# fat.net
KiCad netlist of a schematic drawn in Altium Designer
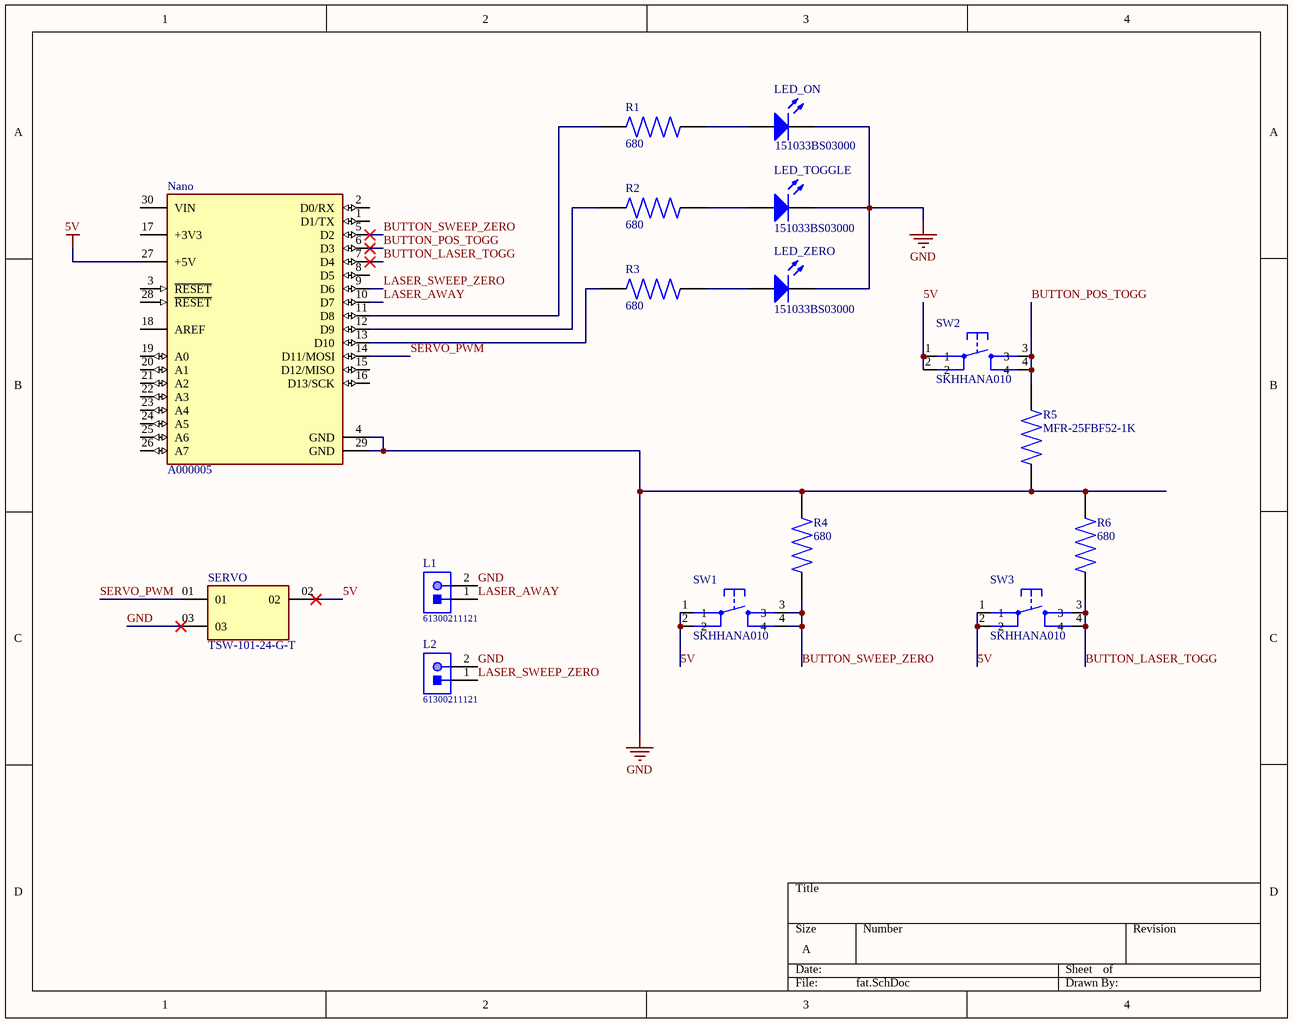
[diagram p0: fat.SchDoc]

(export (version "E")
  (design (tool "Eeschema 10.0.6"))
  (components
    (comp (ref "L1")
      (value "61300211121")
      (footprint "61300211121")
      (description "THT Vertical Pin Header WR-PHD, Pitch 2.54 mm, Single Row, 2 pins")
      (fields (field (name "MANUFACTURER") "Wurth Elektronik") (field (name "PUBLISHER") "WurthElektronik"))
      (libsource (lib "Altium Content Vault") (part "WE-CN-1P-M-R2"))
    )
    (comp (ref "L2")
      (value "61300211121")
      (footprint "61300211121")
      (description "THT Vertical Pin Header WR-PHD, Pitch 2.54 mm, Single Row, 2 pins")
      (fields (field (name "MANUFACTURER") "Wurth Elektronik") (field (name "PUBLISHER") "WurthElektronik"))
      (libsource (lib "Altium Content Vault") (part "WE-CN-1P-M-R2"))
    )
    (comp (ref "LED_ON")
      (value "151033BS03000")
      (footprint "Type 3mm")
      (description "THT LED round mono-color waterclear, WL-TMRW , Blue")
      (fields (field (name "MANUFACTURER") "Wuerth Elektronik"))
      (libsource (lib "Altium Content Vault") (part "WE-LED_K1A2-2"))
    )
    (comp (ref "LED_TOGGLE")
      (value "151033BS03000")
      (footprint "Type 3mm")
      (description "THT LED round mono-color waterclear, WL-TMRW , Blue")
      (fields (field (name "MANUFACTURER") "Wuerth Elektronik"))
      (libsource (lib "Altium Content Vault") (part "WE-LED_K1A2-2"))
    )
    (comp (ref "LED_ZERO")
      (value "151033BS03000")
      (footprint "Type 3mm")
      (description "THT LED round mono-color waterclear, WL-TMRW , Blue")
      (fields (field (name "MANUFACTURER") "Wuerth Elektronik"))
      (libsource (lib "Altium Content Vault") (part "WE-LED_K1A2-2"))
    )
    (comp (ref "Nano")
      (value "A000005")
      (footprint "FP-A000005-MFG")
      (description "ARDUINO NANO ATMEGA328 EVAL BRD")
      (libsource (lib "Altium Content Vault") (part "d190c066e99afd1c6882cf92e11b2cc"))
    )
    (comp (ref "R1")
      (value "680")
      (footprint "RESAD1100W55L680D260")
      (description "1.07 kOhms Â±1% 0.25W, 1/4W Through Hole Resistor Axial - Metal Film")
      (fields (field (name "MF") "Yageo") (field (name "MP") "MFR-25FBF52-1K"))
      (libsource (lib "MFR-25FBF52-1K") (part "MFR-25FBF52-1K"))
    )
    (comp (ref "R2")
      (value "680")
      (footprint "RESAD1100W55L680D260")
      (description "1.07 kOhms Â±1% 0.25W, 1/4W Through Hole Resistor Axial - Metal Film")
      (fields (field (name "MF") "Yageo") (field (name "MP") "MFR-25FBF52-1K"))
      (libsource (lib "MFR-25FBF52-1K") (part "MFR-25FBF52-1K"))
    )
    (comp (ref "R3")
      (value "680")
      (footprint "RESAD1100W55L680D260")
      (description "1.07 kOhms Â±1% 0.25W, 1/4W Through Hole Resistor Axial - Metal Film")
      (fields (field (name "MF") "Yageo") (field (name "MP") "MFR-25FBF52-1K"))
      (libsource (lib "MFR-25FBF52-1K") (part "MFR-25FBF52-1K"))
    )
    (comp (ref "R4")
      (value "680")
      (footprint "RESAD1100W55L680D260")
      (description "1.07 kOhms Â±1% 0.25W, 1/4W Through Hole Resistor Axial - Metal Film")
      (fields (field (name "MF") "Yageo") (field (name "MP") "MFR-25FBF52-1K"))
      (libsource (lib "MFR-25FBF52-1K") (part "MFR-25FBF52-1K"))
    )
    (comp (ref "R5")
      (value "MFR-25FBF52-1K")
      (footprint "RESAD1100W55L680D260")
      (description "1.07 kOhms Â±1% 0.25W, 1/4W Through Hole Resistor Axial - Metal Film")
      (fields (field (name "MF") "Yageo"))
      (libsource (lib "MFR-25FBF52-1K") (part "MFR-25FBF52-1K"))
    )
    (comp (ref "R6")
      (value "680")
      (footprint "RESAD1100W55L680D260")
      (description "1.07 kOhms Â±1% 0.25W, 1/4W Through Hole Resistor Axial - Metal Film")
      (fields (field (name "MF") "Yageo") (field (name "MP") "MFR-25FBF52-1K"))
      (libsource (lib "MFR-25FBF52-1K") (part "MFR-25FBF52-1K"))
    )
    (comp (ref "SERVO")
      (value "TSW-101-24-G-T")
      (footprint "SAMTEC_TSW-101-24-G-T")
      (description "Connector Header Through Hole 3 position -")
      (fields (field (name "MF") "Samtec"))
      (libsource (lib "TSW-101-24-G-T") (part "TSW-101-24-G-T"))
    )
    (comp (ref "SW1")
      (value "SKHHANA010")
      (footprint "SW_SKHHANA010")
      (description "Switch Tactile N.O. SPST Round Button PC Pins 0.05A 12VDC 0.98N Thru-Hole Bulk")
      (fields (field (name "MF") "ALPS"))
      (libsource (lib "SKHHANA010") (part "SKHHANA010"))
    )
    (comp (ref "SW2")
      (value "SKHHANA010")
      (footprint "SW_SKHHANA010")
      (description "Switch Tactile N.O. SPST Round Button PC Pins 0.05A 12VDC 0.98N Thru-Hole Bulk")
      (fields (field (name "MF") "ALPS"))
      (libsource (lib "SKHHANA010") (part "SKHHANA010"))
    )
    (comp (ref "SW3")
      (value "SKHHANA010")
      (footprint "SW_SKHHANA010")
      (description "Switch Tactile N.O. SPST Round Button PC Pins 0.05A 12VDC 0.98N Thru-Hole Bulk")
      (fields (field (name "MF") "ALPS"))
      (libsource (lib "SKHHANA010") (part "SKHHANA010"))
    )
  )
  (nets
    (net (code "1") (name "/BUTTON_LASER_TOGG") (class "Default")
      (node (ref "Nano") (pin "7") (pinfunction "D4_7") (pintype "bidirectional"))
      (node (ref "R6") (pin "2") (pinfunction "2_2") (pintype "passive"))
      (node (ref "SW3") (pin "3") (pinfunction "3_3") (pintype "passive"))
      (node (ref "SW3") (pin "4") (pinfunction "4_4") (pintype "passive"))
    )
    (net (code "2") (name "/BUTTON_POS_TOGG") (class "Default")
      (node (ref "Nano") (pin "6") (pinfunction "D3_6") (pintype "bidirectional"))
      (node (ref "R5") (pin "1") (pinfunction "1_1") (pintype "passive"))
      (node (ref "SW2") (pin "3") (pinfunction "3_3") (pintype "passive"))
      (node (ref "SW2") (pin "4") (pinfunction "4_4") (pintype "passive"))
    )
    (net (code "3") (name "/BUTTON_SWEEP_ZERO") (class "Default")
      (node (ref "Nano") (pin "5") (pinfunction "D2_5") (pintype "bidirectional"))
      (node (ref "R4") (pin "2") (pinfunction "2_2") (pintype "passive"))
      (node (ref "SW1") (pin "3") (pinfunction "3_3") (pintype "passive"))
      (node (ref "SW1") (pin "4") (pinfunction "4_4") (pintype "passive"))
    )
    (net (code "4") (name "/LASER_AWAY") (class "Default")
      (node (ref "L1") (pin "1") (pinfunction "1_1") (pintype "passive"))
      (node (ref "Nano") (pin "10") (pinfunction "D7_10") (pintype "bidirectional"))
    )
    (net (code "5") (name "/LASER_SWEEP_ZERO") (class "Default")
      (node (ref "L2") (pin "1") (pinfunction "1_1") (pintype "passive"))
      (node (ref "Nano") (pin "9") (pinfunction "D6_9") (pintype "bidirectional"))
    )
    (net (code "6") (name "/SERVO_PWM") (class "Default")
      (node (ref "Nano") (pin "14") (pinfunction "D11/MOSI_14") (pintype "bidirectional"))
      (node (ref "SERVO") (pin "01") (pinfunction "01_01") (pintype "passive"))
    )
    (net (code "7") (name "5V") (class "Default")
      (node (ref "Nano") (pin "27") (pinfunction "+5V_27") (pintype "power_in"))
      (node (ref "SERVO") (pin "02") (pinfunction "02_02") (pintype "passive"))
      (node (ref "SW1") (pin "1") (pinfunction "1_1") (pintype "passive"))
      (node (ref "SW1") (pin "2") (pinfunction "2_2") (pintype "passive"))
      (node (ref "SW2") (pin "1") (pinfunction "1_1") (pintype "passive"))
      (node (ref "SW2") (pin "2") (pinfunction "2_2") (pintype "passive"))
      (node (ref "SW3") (pin "1") (pinfunction "1_1") (pintype "passive"))
      (node (ref "SW3") (pin "2") (pinfunction "2_2") (pintype "passive"))
    )
    (net (code "8") (name "GND") (class "Default")
      (node (ref "L1") (pin "2") (pinfunction "2_2") (pintype "passive"))
      (node (ref "L2") (pin "2") (pinfunction "2_2") (pintype "passive"))
      (node (ref "LED_ON") (pin "1") (pinfunction "K_1") (pintype "passive"))
      (node (ref "LED_TOGGLE") (pin "1") (pinfunction "K_1") (pintype "passive"))
      (node (ref "LED_ZERO") (pin "1") (pinfunction "K_1") (pintype "passive"))
      (node (ref "Nano") (pin "29") (pinfunction "GND_29") (pintype "power_in"))
      (node (ref "Nano") (pin "4") (pinfunction "GND_4") (pintype "power_in"))
      (node (ref "R4") (pin "1") (pinfunction "1_1") (pintype "passive"))
      (node (ref "R5") (pin "2") (pinfunction "2_2") (pintype "passive"))
      (node (ref "R6") (pin "1") (pinfunction "1_1") (pintype "passive"))
      (node (ref "SERVO") (pin "03") (pinfunction "03_03") (pintype "passive"))
    )
    (net (code "9") (name "Net-(LED_ON-A)") (class "Default")
      (node (ref "LED_ON") (pin "2") (pinfunction "A_2") (pintype "passive"))
      (node (ref "R1") (pin "2") (pinfunction "2_2") (pintype "passive"))
    )
    (net (code "10") (name "Net-(LED_TOGGLE-A)") (class "Default")
      (node (ref "LED_TOGGLE") (pin "2") (pinfunction "A_2") (pintype "passive"))
      (node (ref "R2") (pin "2") (pinfunction "2_2") (pintype "passive"))
    )
    (net (code "11") (name "Net-(LED_ZERO-A)") (class "Default")
      (node (ref "LED_ZERO") (pin "2") (pinfunction "A_2") (pintype "passive"))
      (node (ref "R3") (pin "2") (pinfunction "2_2") (pintype "passive"))
    )
    (net (code "12") (name "Net-(Nano-D8)") (class "Default")
      (node (ref "Nano") (pin "11") (pinfunction "D8_11") (pintype "bidirectional"))
      (node (ref "R1") (pin "1") (pinfunction "1_1") (pintype "passive"))
    )
    (net (code "13") (name "Net-(Nano-D9)") (class "Default")
      (node (ref "Nano") (pin "12") (pinfunction "D9_12") (pintype "bidirectional"))
      (node (ref "R2") (pin "1") (pinfunction "1_1") (pintype "passive"))
    )
    (net (code "14") (name "Net-(Nano-D10)") (class "Default")
      (node (ref "Nano") (pin "13") (pinfunction "D10_13") (pintype "bidirectional"))
      (node (ref "R3") (pin "1") (pinfunction "1_1") (pintype "passive"))
    )
    (net (code "15") (name "unconnected-(Nano-+3V3-Pad17)") (class "Default")
      (node (ref "Nano") (pin "17") (pinfunction "+3V3_17") (pintype "power_in"))
    )
    (net (code "16") (name "unconnected-(Nano-A0-Pad19)") (class "Default")
      (node (ref "Nano") (pin "19") (pinfunction "A0_19") (pintype "bidirectional"))
    )
    (net (code "17") (name "unconnected-(Nano-A1-Pad20)") (class "Default")
      (node (ref "Nano") (pin "20") (pinfunction "A1_20") (pintype "bidirectional"))
    )
    (net (code "18") (name "unconnected-(Nano-A2-Pad21)") (class "Default")
      (node (ref "Nano") (pin "21") (pinfunction "A2_21") (pintype "bidirectional"))
    )
    (net (code "19") (name "unconnected-(Nano-A3-Pad22)") (class "Default")
      (node (ref "Nano") (pin "22") (pinfunction "A3_22") (pintype "bidirectional"))
    )
    (net (code "20") (name "unconnected-(Nano-A4-Pad23)") (class "Default")
      (node (ref "Nano") (pin "23") (pinfunction "A4_23") (pintype "bidirectional"))
    )
    (net (code "21") (name "unconnected-(Nano-A5-Pad24)") (class "Default")
      (node (ref "Nano") (pin "24") (pinfunction "A5_24") (pintype "bidirectional"))
    )
    (net (code "22") (name "unconnected-(Nano-A6-Pad25)") (class "Default")
      (node (ref "Nano") (pin "25") (pinfunction "A6_25") (pintype "bidirectional"))
    )
    (net (code "23") (name "unconnected-(Nano-A7-Pad26)") (class "Default")
      (node (ref "Nano") (pin "26") (pinfunction "A7_26") (pintype "bidirectional"))
    )
    (net (code "24") (name "unconnected-(Nano-AREF-Pad18)") (class "Default")
      (node (ref "Nano") (pin "18") (pinfunction "AREF_18") (pintype "passive"))
    )
    (net (code "25") (name "unconnected-(Nano-D0{slash}RX-Pad2)") (class "Default")
      (node (ref "Nano") (pin "2") (pinfunction "D0/RX_2") (pintype "bidirectional"))
    )
    (net (code "26") (name "unconnected-(Nano-D1{slash}TX-Pad1)") (class "Default")
      (node (ref "Nano") (pin "1") (pinfunction "D1/TX_1") (pintype "bidirectional"))
    )
    (net (code "27") (name "unconnected-(Nano-D5-Pad8)") (class "Default")
      (node (ref "Nano") (pin "8") (pinfunction "D5_8") (pintype "bidirectional"))
    )
    (net (code "28") (name "unconnected-(Nano-D12{slash}MISO-Pad15)") (class "Default")
      (node (ref "Nano") (pin "15") (pinfunction "D12/MISO_15") (pintype "bidirectional"))
    )
    (net (code "29") (name "unconnected-(Nano-D13{slash}SCK-Pad16)") (class "Default")
      (node (ref "Nano") (pin "16") (pinfunction "D13/SCK_16") (pintype "bidirectional"))
    )
    (net (code "30") (name "unconnected-(Nano-VIN-Pad30)") (class "Default")
      (node (ref "Nano") (pin "30") (pinfunction "VIN_30") (pintype "power_in"))
    )
    (net (code "31") (name "unconnected-(Nano-~{RESET}-Pad3)") (class "Default")
      (node (ref "Nano") (pin "3") (pinfunction "~{RESET}_3") (pintype "input"))
    )
    (net (code "32") (name "unconnected-(Nano-~{RESET}-Pad28)") (class "Default")
      (node (ref "Nano") (pin "28") (pinfunction "~{RESET}_28") (pintype "input"))
    )
  )
)
